# Power.net
KiCad netlist of a schematic drawn in Altium Designer
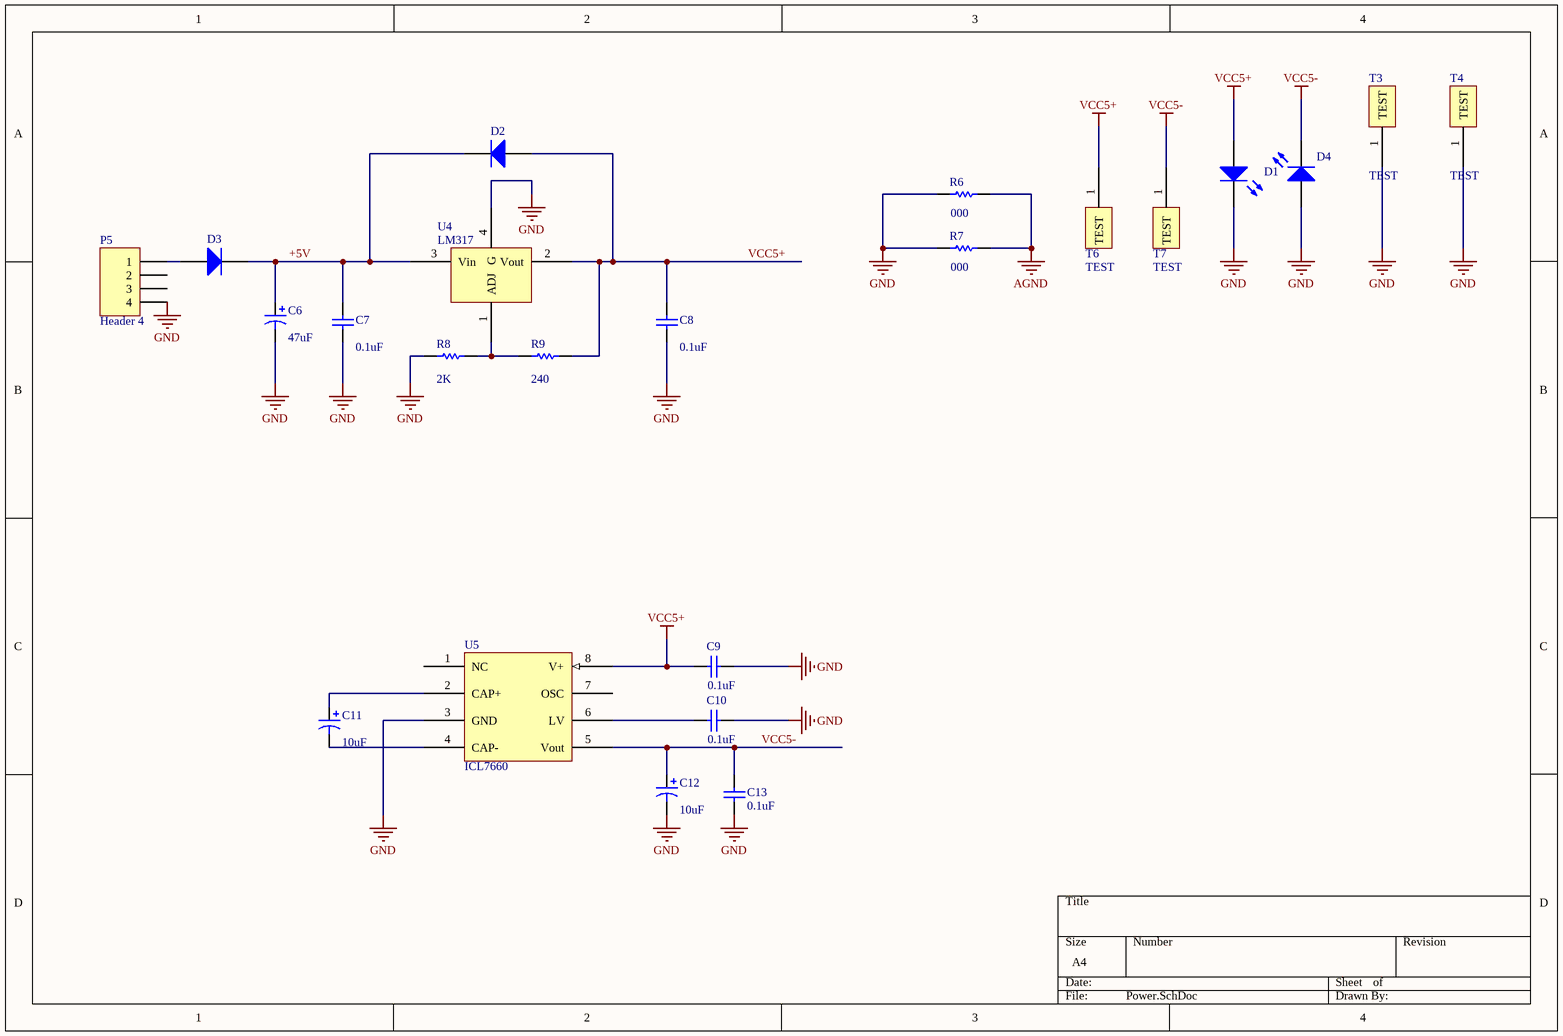
[diagram p0: Power.SchDoc]

(export (version "E")
  (design (tool "Eeschema 10.0.6"))
  (components
    (comp (ref "C6")
      (value "47uF")
      (footprint "6032")
      (description "Polarized Capacitor (Surface Mount)")
      (fields (field (name "Comment") "Cap Pol3") (field (name "PUBLISHER") "Altium Limited"))
      (libsource (lib "Miscellaneous Devices") (part "Cap Pol3"))
    )
    (comp (ref "C7")
      (value "0.1uF")
      (footprint "1206")
      (description "Capacitor (Semiconductor SIM Model)")
      (fields (field (name "Comment") "Cap Semi") (field (name "PUBLISHER") "Altium Limited"))
      (libsource (lib "Miscellaneous Devices") (part "Cap Semi"))
    )
    (comp (ref "C8")
      (value "0.1uF")
      (footprint "1206")
      (description "Capacitor (Semiconductor SIM Model)")
      (fields (field (name "Comment") "Cap Semi") (field (name "PUBLISHER") "Altium Limited"))
      (libsource (lib "Miscellaneous Devices") (part "Cap Semi"))
    )
    (comp (ref "C9")
      (value "0.1uF")
      (footprint "1206")
      (description "Capacitor (Semiconductor SIM Model)")
      (fields (field (name "Comment") "Cap Semi") (field (name "PUBLISHER") "Altium Limited"))
      (libsource (lib "Miscellaneous Devices") (part "Cap Semi"))
    )
    (comp (ref "C10")
      (value "0.1uF")
      (footprint "1206")
      (description "Capacitor (Semiconductor SIM Model)")
      (fields (field (name "Comment") "Cap Semi") (field (name "PUBLISHER") "Altium Limited"))
      (libsource (lib "Miscellaneous Devices") (part "Cap Semi"))
    )
    (comp (ref "C11")
      (value "10uF")
      (footprint "1206")
      (description "Polarized Capacitor (Surface Mount)")
      (fields (field (name "Comment") "Cap Pol3") (field (name "PUBLISHER") "Altium Limited"))
      (libsource (lib "Miscellaneous Devices") (part "Cap Pol3"))
    )
    (comp (ref "C12")
      (value "10uF")
      (footprint "1206")
      (description "Polarized Capacitor (Surface Mount)")
      (fields (field (name "Comment") "Cap Pol3") (field (name "PUBLISHER") "Altium Limited"))
      (libsource (lib "Miscellaneous Devices") (part "Cap Pol3"))
    )
    (comp (ref "C13")
      (value "0.1uF")
      (footprint "1206")
      (description "Capacitor (Semiconductor SIM Model)")
      (fields (field (name "Comment") "Cap Semi") (field (name "PUBLISHER") "Altium Limited"))
      (libsource (lib "Miscellaneous Devices") (part "Cap Semi"))
    )
    (comp (ref "D1")
      (value "LED2")
      (footprint "0805_LED")
      (description "Typical RED, GREEN, YELLOW, AMBER GaAs LED")
      (fields (field (name "PUBLISHER") "Altium Limited"))
      (libsource (lib "Miscellaneous Devices") (part "LED2"))
    )
    (comp (ref "D2")
      (value "Diode")
      (footprint "1N5824")
      (description "Default Diode")
      (fields (field (name "PUBLISHER") "Altium Limited"))
      (libsource (lib "Miscellaneous Devices") (part "Diode"))
    )
    (comp (ref "D3")
      (value "Diode")
      (footprint "1N5824")
      (description "Default Diode")
      (fields (field (name "PUBLISHER") "Altium Limited"))
      (libsource (lib "Miscellaneous Devices") (part "Diode"))
    )
    (comp (ref "D4")
      (value "LED2")
      (footprint "0805_LED")
      (description "Typical RED, GREEN, YELLOW, AMBER GaAs LED")
      (fields (field (name "PUBLISHER") "Altium Limited"))
      (libsource (lib "Miscellaneous Devices") (part "LED2"))
    )
    (comp (ref "P5")
      (value "Header 4")
      (footprint "HDR1X4")
      (description "Header, 4-Pin")
      (fields (field (name "PUBLISHER") "Altium Limited"))
      (libsource (lib "Miscellaneous Connectors") (part "Header 4"))
    )
    (comp (ref "R6")
      (value "000")
      (footprint "1206")
      (description "Semiconductor Resistor")
      (fields (field (name "Comment") "Res Semi") (field (name "PUBLISHER") "Altium Limited"))
      (libsource (lib "Miscellaneous Devices") (part "Res Semi"))
    )
    (comp (ref "R7")
      (value "000")
      (footprint "0805R")
      (description "Semiconductor Resistor")
      (fields (field (name "Comment") "Res Semi") (field (name "PUBLISHER") "Altium Limited"))
      (libsource (lib "Miscellaneous Devices") (part "Res Semi"))
    )
    (comp (ref "R8")
      (value "2K")
      (footprint "1206")
      (description "Semiconductor Resistor")
      (fields (field (name "Comment") "Res Semi") (field (name "PUBLISHER") "Altium Limited"))
      (libsource (lib "Miscellaneous Devices") (part "Res Semi"))
    )
    (comp (ref "R9")
      (value "240")
      (footprint "1206")
      (description "Semiconductor Resistor")
      (fields (field (name "Comment") "Res Semi") (field (name "PUBLISHER") "Altium Limited"))
      (libsource (lib "Miscellaneous Devices") (part "Res Semi"))
    )
    (comp (ref "T3") (value "TEST") (footprint "TEST") (libsource (lib "") (part "TEST_1")))
    (comp (ref "T4") (value "TEST") (footprint "TEST") (libsource (lib "") (part "TEST_1")))
    (comp (ref "T6") (value "TEST") (footprint "TEST_2") (libsource (lib "Schlib1") (part "TEST")))
    (comp (ref "T7") (value "TEST") (footprint "TEST_2") (libsource (lib "Schlib1") (part "TEST")))
    (comp (ref "U4") (value "LM317") (footprint "SOT223") (libsource (lib "Schlib1") (part "LM317")))
    (comp (ref "U5") (value "ICL7660") (footprint "SO8") (libsource (lib "Schlib1") (part "ICL7660")))
  )
  (nets
    (net (code "1") (name "/+5V") (class "Default")
      (node (ref "C6") (pin "1") (pinfunction "1_1") (pintype "passive"))
      (node (ref "C7") (pin "2") (pinfunction "2_2") (pintype "passive"))
      (node (ref "D2") (pin "2") (pinfunction "K_2") (pintype "passive"))
      (node (ref "D3") (pin "2") (pinfunction "K_2") (pintype "passive"))
      (node (ref "U4") (pin "3") (pinfunction "Vin_3") (pintype "passive"))
    )
    (net (code "2") (name "AGND") (class "Default")
      (node (ref "R6") (pin "2") (pinfunction "2_2") (pintype "passive"))
      (node (ref "R7") (pin "2") (pinfunction "2_2") (pintype "passive"))
    )
    (net (code "3") (name "GND") (class "Default")
      (node (ref "C10") (pin "2") (pinfunction "2_2") (pintype "passive"))
      (node (ref "C12") (pin "2") (pinfunction "2_2") (pintype "passive"))
      (node (ref "C13") (pin "1") (pinfunction "1_1") (pintype "passive"))
      (node (ref "C6") (pin "2") (pinfunction "2_2") (pintype "passive"))
      (node (ref "C7") (pin "1") (pinfunction "1_1") (pintype "passive"))
      (node (ref "C8") (pin "2") (pinfunction "2_2") (pintype "passive"))
      (node (ref "C9") (pin "2") (pinfunction "2_2") (pintype "passive"))
      (node (ref "D1") (pin "2") (pinfunction "K_2") (pintype "passive"))
      (node (ref "D4") (pin "1") (pinfunction "A_1") (pintype "passive"))
      (node (ref "P5") (pin "4") (pinfunction "4_4") (pintype "passive"))
      (node (ref "R6") (pin "1") (pinfunction "1_1") (pintype "passive"))
      (node (ref "R7") (pin "1") (pinfunction "1_1") (pintype "passive"))
      (node (ref "R8") (pin "1") (pinfunction "1_1") (pintype "passive"))
      (node (ref "T3") (pin "1") (pinfunction "TEST_1") (pintype "passive"))
      (node (ref "T4") (pin "1") (pinfunction "TEST_1") (pintype "passive"))
      (node (ref "U4") (pin "4") (pinfunction "G_4") (pintype "passive"))
      (node (ref "U5") (pin "3") (pinfunction "GND_3") (pintype "power_in"))
    )
    (net (code "4") (name "Net-(D3-A)") (class "Default")
      (node (ref "D3") (pin "1") (pinfunction "A_1") (pintype "passive"))
      (node (ref "P5") (pin "1") (pinfunction "1_1") (pintype "passive"))
    )
    (net (code "5") (name "Net-(U4-ADJ)") (class "Default")
      (node (ref "R8") (pin "2") (pinfunction "2_2") (pintype "passive"))
      (node (ref "R9") (pin "1") (pinfunction "1_1") (pintype "passive"))
      (node (ref "U4") (pin "1") (pinfunction "ADJ_1") (pintype "passive"))
    )
    (net (code "6") (name "Net-(U5-CAP+)") (class "Default")
      (node (ref "C11") (pin "1") (pinfunction "1_1") (pintype "passive"))
      (node (ref "U5") (pin "2") (pinfunction "CAP+_2") (pintype "passive"))
    )
    (net (code "7") (name "Net-(U5-CAP-)") (class "Default")
      (node (ref "C11") (pin "2") (pinfunction "2_2") (pintype "passive"))
      (node (ref "U5") (pin "4") (pinfunction "CAP-_4") (pintype "passive"))
    )
    (net (code "8") (name "Net-(U5-LV)") (class "Default")
      (node (ref "C10") (pin "1") (pinfunction "1_1") (pintype "passive"))
      (node (ref "U5") (pin "6") (pinfunction "LV_6") (pintype "passive"))
    )
    (net (code "9") (name "VCC5+") (class "Default")
      (node (ref "C8") (pin "1") (pinfunction "1_1") (pintype "passive"))
      (node (ref "C9") (pin "1") (pinfunction "1_1") (pintype "passive"))
      (node (ref "D1") (pin "1") (pinfunction "A_1") (pintype "passive"))
      (node (ref "D2") (pin "1") (pinfunction "A_1") (pintype "passive"))
      (node (ref "R9") (pin "2") (pinfunction "2_2") (pintype "passive"))
      (node (ref "T6") (pin "1") (pinfunction "TEST_1") (pintype "passive"))
      (node (ref "U4") (pin "2") (pinfunction "Vout_2") (pintype "passive"))
      (node (ref "U5") (pin "8") (pinfunction "V+_8") (pintype "input"))
    )
    (net (code "10") (name "VCC5-") (class "Default")
      (node (ref "C12") (pin "1") (pinfunction "1_1") (pintype "passive"))
      (node (ref "C13") (pin "2") (pinfunction "2_2") (pintype "passive"))
      (node (ref "D4") (pin "2") (pinfunction "K_2") (pintype "passive"))
      (node (ref "T7") (pin "1") (pinfunction "TEST_1") (pintype "passive"))
      (node (ref "U5") (pin "5") (pinfunction "Vout_5") (pintype "passive"))
    )
    (net (code "11") (name "unconnected-(P5-Pad2)") (class "Default")
      (node (ref "P5") (pin "2") (pinfunction "2_2") (pintype "passive"))
    )
    (net (code "12") (name "unconnected-(P5-Pad3)") (class "Default")
      (node (ref "P5") (pin "3") (pinfunction "3_3") (pintype "passive"))
    )
    (net (code "13") (name "unconnected-(U5-NC-Pad1)") (class "Default")
      (node (ref "U5") (pin "1") (pinfunction "NC_1") (pintype "passive"))
    )
    (net (code "14") (name "unconnected-(U5-OSC-Pad7)") (class "Default")
      (node (ref "U5") (pin "7") (pinfunction "OSC_7") (pintype "passive"))
    )
  )
)
